# 02-POWER_SUPPLY.net
KiCad netlist of a schematic drawn in Altium Designer
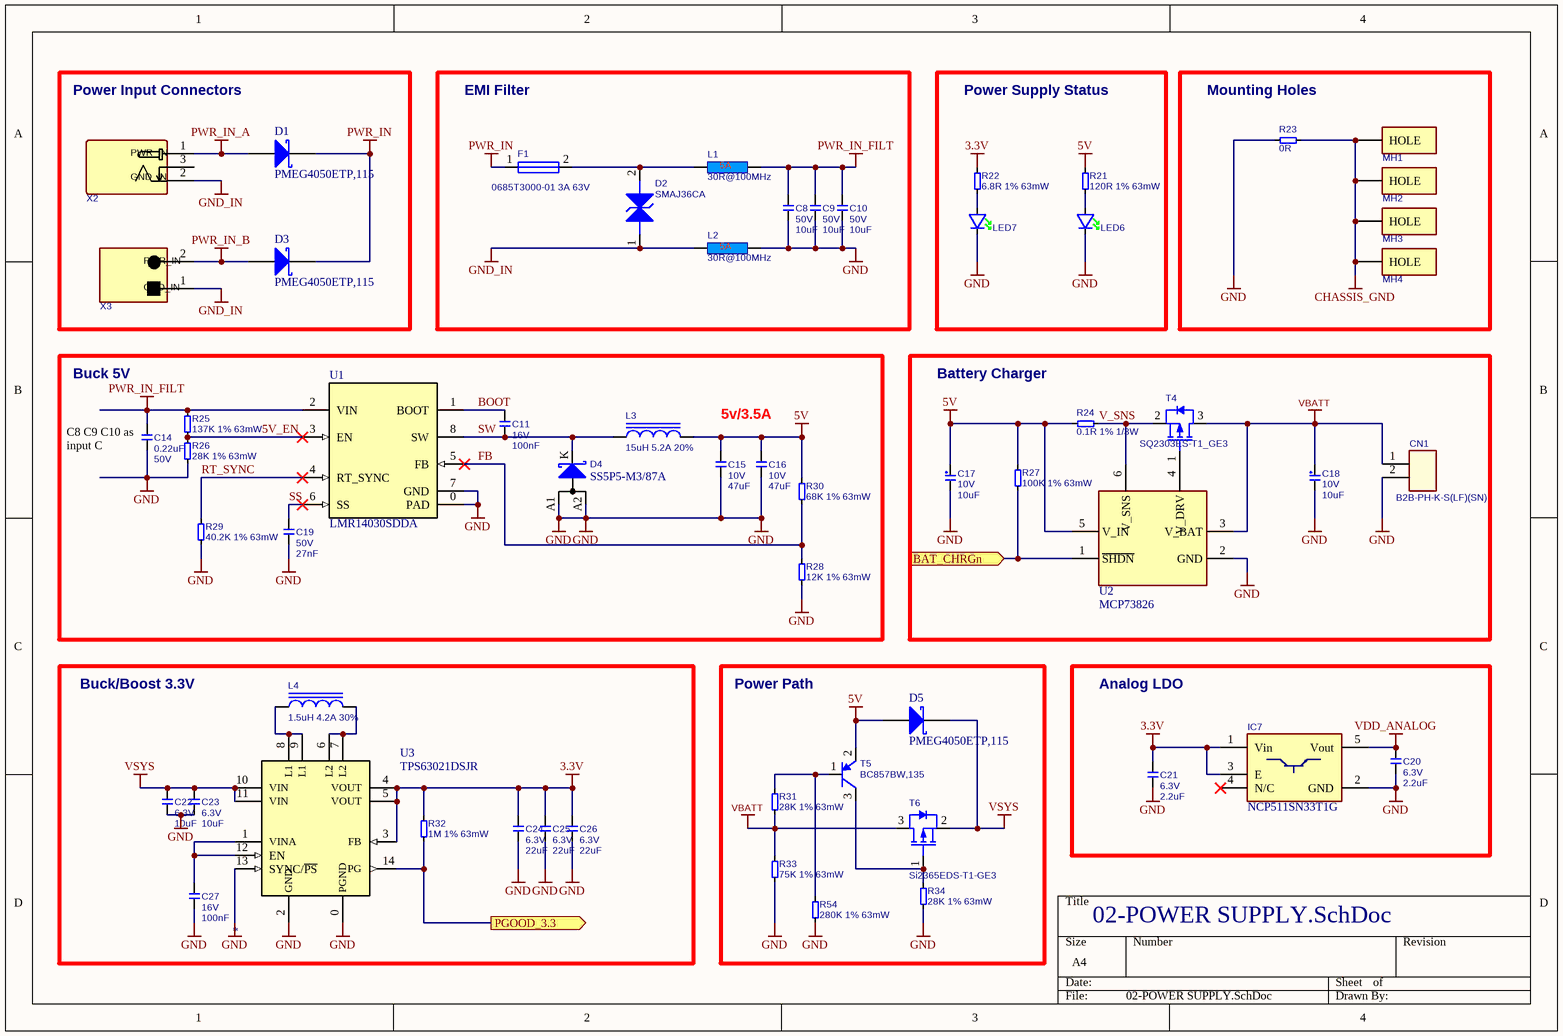
[diagram p0: 02-POWER SUPPLY.SchDoc]

(export (version "E")
  (design (tool "Eeschema 10.0.6"))
  (components
    (comp (ref "C8")
      (value "10uF")
      (footprint "CAPC3225X160N")
      (description "Capacitor Ceramic X5R 10uF 50V 20% 1210")
      (fields
        (field (name "TOLERANCE") "20%")
        (field (name "RATING") "50V")
        (field (name "Comment") "10uF 50V 20% X5R")
      )
      (libsource (lib "AI Gateway - Carrier") (part "C-10uF-50V-20%-1210"))
    )
    (comp (ref "C9")
      (value "10uF")
      (footprint "CAPC3225X160N")
      (description "Capacitor Ceramic X5R 10uF 50V 20% 1210")
      (fields
        (field (name "TOLERANCE") "20%")
        (field (name "RATING") "50V")
        (field (name "Comment") "10uF 50V 20% X5R")
      )
      (libsource (lib "AI Gateway - Carrier") (part "C-10uF-50V-20%-1210"))
    )
    (comp (ref "C10")
      (value "10uF")
      (footprint "CAPC3225X160N")
      (description "Capacitor Ceramic X5R 10uF 50V 20% 1210")
      (fields
        (field (name "TOLERANCE") "20%")
        (field (name "RATING") "50V")
        (field (name "Comment") "10uF 50V 20% X5R")
      )
      (libsource (lib "AI Gateway - Carrier") (part "C-10uF-50V-20%-1210"))
    )
    (comp (ref "C11")
      (value "100nF")
      (footprint "CAPC1005X60N")
      (description "Capacitor Ceramic X7R 100nF 16V 10% 0603")
      (fields
        (field (name "TOLERANCE") "10%")
        (field (name "RATING") "16V")
        (field (name "Comment") "100nF 16V 10% X7R")
      )
      (libsource (lib "AI Gateway - Carrier") (part "C-100nF-16V-10%-0603"))
    )
    (comp (ref "C14")
      (value "0.22uF")
      (footprint "T_CAPC0805X125N")
      (description "Capacitor Ceramic X7R 0.22uF 50V 10% 0805")
      (fields
        (field (name "TOLERANCE") "10%")
        (field (name "RATING") "50V")
        (field (name "Comment") "0.22uF 50V 10% X7R")
      )
      (libsource (lib "AI Gateway - Carrier") (part "C-0.22uF-50V-10%-0805"))
    )
    (comp (ref "C15")
      (value "47uF")
      (footprint "CAPC3225X160N")
      (description "Capacitor Ceramic X5R 47uF 10V 20% 1210")
      (fields
        (field (name "TOLERANCE") "20%")
        (field (name "RATING") "10V")
        (field (name "Comment") "47uF 10V 20% X5R")
      )
      (libsource (lib "AI Gateway - Carrier") (part "C-47uF-10V-20%-1210"))
    )
    (comp (ref "C16")
      (value "47uF")
      (footprint "CAPC3225X160N")
      (description "Capacitor Ceramic X5R 47uF 10V 20% 1210")
      (fields
        (field (name "TOLERANCE") "20%")
        (field (name "RATING") "10V")
        (field (name "Comment") "47uF 10V 20% X5R")
      )
      (libsource (lib "AI Gateway - Carrier") (part "C-47uF-10V-20%-1210"))
    )
    (comp (ref "C17")
      (value "10uF")
      (footprint "T_CAPC1206X180N")
      (description "Capacitor Tantalum 10uF 10V 20% 1206")
      (fields
        (field (name "TOLERANCE") "20%")
        (field (name "RATING") "10V")
        (field (name "Comment") "10uF 10V 20% Tantalum")
      )
      (libsource (lib "AI Gateway - Carrier") (part "C-10uF-10V-20%-1206"))
    )
    (comp (ref "C18")
      (value "10uF")
      (footprint "T_CAPC1206X180N")
      (description "Capacitor Tantalum 10uF 10V 20% 1206")
      (fields
        (field (name "TOLERANCE") "20%")
        (field (name "RATING") "10V")
        (field (name "Comment") "10uF 10V 20% Tantalum")
      )
      (libsource (lib "AI Gateway - Carrier") (part "C-10uF-10V-20%-1206"))
    )
    (comp (ref "C19")
      (value "27nF")
      (footprint "T_CAPC0603X33N")
      (description "Capacitor Ceramic X7R 27nF 50V 10% 0603")
      (fields
        (field (name "TOLERANCE") "10%")
        (field (name "RATING") "50V")
        (field (name "Comment") "27nF 50V 20% X7R")
      )
      (libsource (lib "AI Gateway - Carrier") (part "C-27nF-50V-10%-0603"))
    )
    (comp (ref "C20")
      (value "2.2uF")
      (footprint "T_CAPC0603X33N")
      (description "Capacitor Ceramic X5R 2.2uF 6.3V 20% 0603")
      (fields
        (field (name "TOLERANCE") "20%")
        (field (name "RATING") "6.3V")
        (field (name "Comment") "2.2uF 6.3V 20% X5R")
      )
      (libsource (lib "AI Gateway - Carrier") (part "C-2.2uF-6.3V-20%-0603"))
    )
    (comp (ref "C21")
      (value "2.2uF")
      (footprint "T_CAPC0603X33N")
      (description "Capacitor Ceramic X5R 2.2uF 6.3V 20% 0603")
      (fields
        (field (name "TOLERANCE") "20%")
        (field (name "RATING") "6.3V")
        (field (name "Comment") "2.2uF 6.3V 20% X5R")
      )
      (libsource (lib "AI Gateway - Carrier") (part "C-2.2uF-6.3V-20%-0603"))
    )
    (comp (ref "C22")
      (value "10uF")
      (footprint "T_CAPC0603X33N")
      (description "Capacitor Ceramic X5R 10uF 6.3V 20% 0603")
      (fields
        (field (name "TOLERANCE") "20%")
        (field (name "RATING") "6.3V")
        (field (name "Comment") "10uF 6.3V 20% X5R")
      )
      (libsource (lib "AI Gateway - Carrier") (part "C-10uF-6.3V-20%-0603"))
    )
    (comp (ref "C23")
      (value "10uF")
      (footprint "T_CAPC0603X33N")
      (description "Capacitor Ceramic X5R 10uF 6.3V 20% 0603")
      (fields
        (field (name "TOLERANCE") "20%")
        (field (name "RATING") "6.3V")
        (field (name "Comment") "10uF 6.3V 20% X5R")
      )
      (libsource (lib "AI Gateway - Carrier") (part "C-10uF-6.3V-20%-0603"))
    )
    (comp (ref "C24")
      (value "22uF")
      (footprint "T_CAPC0603X33N")
      (description "Capacitor Ceramic X5R 22uF 6.3V 20% 0603")
      (fields
        (field (name "TOLERANCE") "20%")
        (field (name "RATING") "6.3V")
        (field (name "Comment") "22uF 6.3V 20% X5R")
      )
      (libsource (lib "AI Gateway - Carrier") (part "C-22uF-6.3V-20%-0603"))
    )
    (comp (ref "C25")
      (value "22uF")
      (footprint "T_CAPC0603X33N")
      (description "Capacitor Ceramic X5R 22uF 6.3V 20% 0603")
      (fields
        (field (name "TOLERANCE") "20%")
        (field (name "RATING") "6.3V")
        (field (name "Comment") "22uF 6.3V 20% X5R")
      )
      (libsource (lib "AI Gateway - Carrier") (part "C-22uF-6.3V-20%-0603"))
    )
    (comp (ref "C26")
      (value "22uF")
      (footprint "T_CAPC0603X33N")
      (description "Capacitor Ceramic X5R 22uF 6.3V 20% 0603")
      (fields
        (field (name "TOLERANCE") "20%")
        (field (name "RATING") "6.3V")
        (field (name "Comment") "22uF 6.3V 20% X5R")
      )
      (libsource (lib "AI Gateway - Carrier") (part "C-22uF-6.3V-20%-0603"))
    )
    (comp (ref "C27")
      (value "100nF")
      (footprint "CAPC1005X60N")
      (description "Capacitor Ceramic X7R 100nF 16V 10% 0603")
      (fields
        (field (name "TOLERANCE") "10%")
        (field (name "RATING") "16V")
        (field (name "Comment") "100nF 16V 10% X7R")
      )
      (libsource (lib "AI Gateway - Carrier") (part "C-100nF-16V-10%-0603"))
    )
    (comp (ref "CN1")
      (value "B2B-PH-K-S(LF)(SN)")
      (footprint "B2B-PH-K-S(LF)(SN) - duplicate")
      (description "Connector Header Through Hole 2 position 0.079\" (2.00mm)")
      (fields (field (name "MFG") "JST") (field (name "FOOTPRINT CHECKED") "Assign OK, Footprint OK"))
      (libsource (lib "Connectors") (part "CON-JST-B2B-PH-K-S(LF)(SN)"))
    )
    (comp (ref "D1")
      (value "PMEG4050ETP,115")
      (footprint "D_SOD128")
      (description "Diode Schottky 40V 5A Surface Mount CFP5")
      (fields (field (name "MFG") "Nexperia USA Inc."))
      (libsource (lib "AI Gateway - Carrier") (part "D-NXP- PMEG4050ETP,115"))
    )
    (comp (ref "D2")
      (value "SMAJ36CA")
      (footprint "T_LITTLEFUSE_SMAJ30CA")
      (description "58.1V Clamp 6.9A Ipp Tvs Diode Surface Mount DO-214AC (SMA)")
      (fields (field (name "MFG") "Vishay") (field (name "FOOTPRINT CHECKED") "Assign OK, Footprint OK"))
      (libsource (lib "AI Gateway - Carrier") (part "D-Vishay-SMAJ36CA"))
    )
    (comp (ref "D3")
      (value "PMEG4050ETP,115")
      (footprint "D_SOD128")
      (description "Diode Schottky 40V 5A Surface Mount CFP5")
      (fields (field (name "MFG") "Nexperia USA Inc."))
      (libsource (lib "AI Gateway - Carrier") (part "D-NXP- PMEG4050ETP,115"))
    )
    (comp (ref "D4")
      (value "SS5P5-M3/87A")
      (footprint "T_DIOM_TO277A")
      (description "Diode Schottky, SS5P5-M3/87A, 50V(Vrrm), 5A(If)")
      (fields (field (name "MFG") "Vishay"))
      (libsource (lib "Passive") (part "D-Vishay-SS5P5-M3/87A"))
    )
    (comp (ref "D5")
      (value "PMEG4050ETP,115")
      (footprint "D_SOD128")
      (description "Diode Schottky 40V 5A Surface Mount CFP5")
      (fields (field (name "MFG") "Nexperia USA Inc."))
      (libsource (lib "AI Gateway - Carrier") (part "D-NXP- PMEG4050ETP,115"))
    )
    (comp (ref "F1")
      (value "0685T3000-01 3A 63V")
      (footprint "RESC3216N")
      (description "3A 63V AC 63V DC Fuse Board Mount (Cartridge Style Excluded) Surface Mount 1206 (3216 Metric)")
      (fields (field (name "MFG") "BEL") (field (name "POWER") "250mW"))
      (libsource (lib "Passive") (part "F-BEL-3A-63V"))
    )
    (comp (ref "IC7")
      (value "NCP511SN33T1G")
      (footprint "SOT95P279X142-5N")
      (description "NCP511SN33T1G LDO Regulator")
      (fields (field (name "MFG") "ON Semiconductor"))
      (libsource (lib "AIGateway") (part "IC-ON-NCP511SN33T1G"))
    )
    (comp (ref "L1")
      (value "30R@100MHz")
      (footprint "INDC1608X95N")
      (description "30 Ohms @ 100MHz 1 Power Line Ferrite Bead 0603 (1608 Metric) 5A 10mOhm")
      (fields
        (field (name "TOLERANCE") "25%")
        (field (name "MFG") "EXC-ML20A390U")
        (field (name "FOOTPRINT CHECKED") "Ok, Assign Ok")
      )
      (libsource (lib "Passive") (part "L-Murata-30R@100MHz-5A-0603"))
    )
    (comp (ref "L2")
      (value "30R@100MHz")
      (footprint "INDC1608X95N")
      (description "30 Ohms @ 100MHz 1 Power Line Ferrite Bead 0603 (1608 Metric) 5A 10mOhm")
      (fields
        (field (name "TOLERANCE") "25%")
        (field (name "MFG") "EXC-ML20A390U")
        (field (name "FOOTPRINT CHECKED") "Ok, Assign Ok")
      )
      (libsource (lib "Passive") (part "L-Murata-30R@100MHz-5A-0603"))
    )
    (comp (ref "L3")
      (value "15uH 5.2A 20%")
      (footprint "T_INDM125125X80N")
      (description "FIXED IND 15UH 5.2A 28.5MOHM SMD")
      (fields (field (name "MFG") "Bourns Inc."))
      (libsource (lib "AI Gateway - Carrier") (part "L-Bourns-SRR1280-150M"))
    )
    (comp (ref "L4")
      (value "1.5uH 4.2A 30%")
      (footprint "L_NR6028")
      (description "Inductor Ferrite core 1.5uH 4.2A 30%")
      (fields (field (name "MFG") "TAIYO YUDEN"))
      (libsource (lib "Passive") (part "L-1.5uH-4.2A-30%"))
    )
    (comp (ref "LED6")
      (value "150060GS75000")
      (footprint "LEDC1608X80N")
      (description "Green 520nm LED Indication - Discrete 3.2V 0603 (1608 Metric)")
      (fields (field (name "MFG") "Würth Elektronik"))
      (libsource (lib "AI Gateway - Carrier") (part "LED-GREEN-0603"))
    )
    (comp (ref "LED7")
      (value "150060GS75000")
      (footprint "LEDC1608X80N")
      (description "Green 520nm LED Indication - Discrete 3.2V 0603 (1608 Metric)")
      (fields (field (name "MFG") "Würth Elektronik"))
      (libsource (lib "AI Gateway - Carrier") (part "LED-GREEN-0603"))
    )
    (comp (ref "MH1")
      (value "MECH-MountingHoles")
      (footprint "T_MountingHoles")
      (description "PCB Mounting Holes, hole diemeter = 3.2mm, pad diameter = 6.2mm")
      (libsource (lib "Connectors") (part "MECH-MountingHoles"))
    )
    (comp (ref "MH2")
      (value "MECH-MountingHoles")
      (footprint "T_MountingHoles")
      (description "PCB Mounting Holes, hole diemeter = 3.2mm, pad diameter = 6.2mm")
      (libsource (lib "Connectors") (part "MECH-MountingHoles"))
    )
    (comp (ref "MH3")
      (value "MECH-MountingHoles")
      (footprint "T_MountingHoles")
      (description "PCB Mounting Holes, hole diemeter = 3.2mm, pad diameter = 6.2mm")
      (libsource (lib "Connectors") (part "MECH-MountingHoles"))
    )
    (comp (ref "MH4")
      (value "MECH-MountingHoles")
      (footprint "T_MountingHoles")
      (description "PCB Mounting Holes, hole diemeter = 3.2mm, pad diameter = 6.2mm")
      (libsource (lib "Connectors") (part "MECH-MountingHoles"))
    )
    (comp (ref "R21")
      (value "120R 1% 63mW")
      (footprint "RESC1005X40N")
      (description "Resistor 120ohm 63mW 1% 0402")
      (fields (field (name "POWER") "63mW") (field (name "TOLERANCE") "1%"))
      (libsource (lib "AI Gateway - Carrier") (part "R-120R-1%-0402"))
    )
    (comp (ref "R22")
      (value "6.8R 1% 63mW")
      (footprint "RESC1005X40N")
      (description "Resistor 6.8ohm 63mW 1% 0402")
      (fields (field (name "POWER") "63mW") (field (name "TOLERANCE") "1%"))
      (libsource (lib "AI Gateway - Carrier") (part "R-6.8R-1%-0402"))
    )
    (comp (ref "R23")
      (value "0R")
      (footprint "RESC1005X40N")
      (description "Resistor 0ohm 0402")
      (fields (field (name "POWER") "?") (field (name "TOLERANCE") "1%"))
      (libsource (lib "AI Gateway - Carrier") (part "R-0R-0402"))
    )
    (comp (ref "R24")
      (value "0.1R 1% 1/3W")
      (footprint "RESC1608N")
      (description "Resistor 0.1ohm 1/3W 1% 0603")
      (fields (field (name "POWER") "1/3") (field (name "TOLERANCE") "1%"))
      (libsource (lib "AI Gateway - Carrier") (part "R-0.1-1%-0603"))
    )
    (comp (ref "R25")
      (value "137K 1% 63mW")
      (footprint "RESC1005X40N")
      (description "Resistor 137Kohm 63mW 1% 0402")
      (fields
        (field (name "POWER") "63mW")
        (field (name "TOLERANCE") "1%")
        (field (name "SYMBOL CHECKED") "T")
      )
      (libsource (lib "AI Gateway - Carrier") (part "R-137K-1%-0402"))
    )
    (comp (ref "R26")
      (value "28K 1% 63mW")
      (footprint "RESC1005X40N")
      (description "Resistor 28Kohm 63mW 1% 0402")
      (fields
        (field (name "POWER") "63mW")
        (field (name "TOLERANCE") "1%")
        (field (name "SYMBOL CHECKED") "T")
      )
      (libsource (lib "AI Gateway - Carrier") (part "R-28K-1%-0402"))
    )
    (comp (ref "R27")
      (value "100K 1% 63mW")
      (footprint "RESC1005X40N")
      (description "Resistor 100Kohm 63mW 1% 0402")
      (fields (field (name "POWER") "63mW") (field (name "TOLERANCE") "1%"))
      (libsource (lib "AI Gateway - Carrier") (part "R-100K-1%-0402"))
    )
    (comp (ref "R28")
      (value "12K 1% 63mW")
      (footprint "RESC1005X40N")
      (description "Resistor 12Kohm 63mW 1% 0402")
      (fields
        (field (name "POWER") "63mW")
        (field (name "TOLERANCE") "1%")
        (field (name "SYMBOL CHECKED") "T")
      )
      (libsource (lib "AI Gateway - Carrier") (part "R-12K-1%-0402"))
    )
    (comp (ref "R29")
      (value "40.2K 1% 63mW")
      (footprint "RESC1005X40N")
      (description "Resistor 40.2Kohm 63mW 1% 0402")
      (fields
        (field (name "POWER") "63mW")
        (field (name "TOLERANCE") "1%")
        (field (name "SYMBOL CHECKED") "T")
      )
      (libsource (lib "AI Gateway - Carrier") (part "R-40.2K-1%-0402"))
    )
    (comp (ref "R30")
      (value "68K 1% 63mW")
      (footprint "RESC1005X40N")
      (description "Resistor 68Kohm 63mW 1% 0402")
      (fields
        (field (name "POWER") "63mW")
        (field (name "TOLERANCE") "1%")
        (field (name "SYMBOL CHECKED") "T")
      )
      (libsource (lib "AI Gateway - Carrier") (part "R-68K-1%-0402_1"))
    )
    (comp (ref "R31")
      (value "28K 1% 63mW")
      (footprint "RESC1005X40N")
      (description "Resistor 28Kohm 63mW 1% 0402")
      (fields
        (field (name "POWER") "63mW")
        (field (name "TOLERANCE") "1%")
        (field (name "SYMBOL CHECKED") "T")
      )
      (libsource (lib "AI Gateway - Carrier") (part "R-28K-1%-0402"))
    )
    (comp (ref "R32")
      (value "1M 1% 63mW")
      (footprint "RESC1005X40N")
      (description "Resistor 1Mohm 63mW 1% 0402")
      (fields (field (name "POWER") "63mW") (field (name "TOLERANCE") "1%"))
      (libsource (lib "AI Gateway - Carrier") (part "R-1M-1%-0402"))
    )
    (comp (ref "R33")
      (value "75K 1% 63mW")
      (footprint "RESC1005X40N")
      (description "Resistor 75Kohm 63mW 1% 0402")
      (fields (field (name "POWER") "63mW") (field (name "TOLERANCE") "1%"))
      (libsource (lib "AI Gateway - Carrier") (part "R-75K-1%-0402"))
    )
    (comp (ref "R34")
      (value "28K 1% 63mW")
      (footprint "RESC1005X40N")
      (description "Resistor 28Kohm 63mW 1% 0402")
      (fields
        (field (name "POWER") "63mW")
        (field (name "TOLERANCE") "1%")
        (field (name "SYMBOL CHECKED") "T")
      )
      (libsource (lib "AI Gateway - Carrier") (part "R-28K-1%-0402"))
    )
    (comp (ref "R54")
      (value "280K 1% 63mW")
      (footprint "RESC1005X40N")
      (description "Resistor 280Kohm 63mW 1% 0402")
      (fields (field (name "POWER") "63mW") (field (name "TOLERANCE") "1%"))
      (libsource (lib "AI Gateway - Carrier") (part "R-280K-1%-0402"))
    )
    (comp (ref "T4")
      (value "SQ2303ES-T1_GE3")
      (footprint "SOT95P230X110-3N")
      (description "P-Channel 30V 2.5A (Tc) 1.9W (Tc) Surface Mount TO-236 (SOT-23)")
      (fields (field (name "MFG") "VISHAY"))
      (libsource (lib "Passive") (part "T-Vishay-SQ2303ES"))
    )
    (comp (ref "T5")
      (value "BC857BW,135")
      (footprint "SOT65P210X110-3N")
      (description "PNP Transistor NXP BC857BW,135")
      (fields (field (name "MFG") "NXP"))
      (libsource (lib "Passive") (part "T-NXP-BC857BW"))
    )
    (comp (ref "T6")
      (value "Si2365EDS-T1-GE3")
      (footprint "SOT95P230X110-3N")
      (description "MOSFET, P channel Vishay Si2365EDS-T1-GE3")
      (fields (field (name "MFG") "VISHAY"))
      (libsource (lib "AI Gateway - Carrier") (part "T-Vishay-Si2365EDS"))
    )
    (comp (ref "U1")
      (value "LMR14030SDDA")
      (footprint "SOIC127P600X175-9AN-2")
      (fields (field (name "MFG") "Texas Instruments") (field (name "SYMBOL CHECKED") "DMT"))
      (libsource (lib "AI Gateway - Carrier") (part "IC-TI-LMR14030"))
    )
    (comp (ref "U2")
      (value "MCP73826")
      (footprint "SOT95P284X122-6N")
      (description "Charger IC Lithium Ion SOT-23-6")
      (fields (field (name "MFG") "Microchip") (field (name "SYMBOL CHECKED") "D"))
      (libsource (lib "AIGateway") (part "IC-Microchip-MCP73826"))
    )
    (comp (ref "U3")
      (value "TPS63021DSJR")
      (footprint "DSJ14_2P85X1P58")
      (description "Buck-Boost Switching Regulator IC Positive Fixed 3.3V 1 Output 3.5A (Switch) 14-VFDFN Exposed Pad")
      (fields
        (field (name "MFG") "Texas Instruments")
        (field (name "PARAMETER 1") "*")
        (field (name "FOOTPRINT CHECKED") "D")
      )
      (libsource (lib "AIGateway") (part "IC-TI-TPS63021"))
    )
    (comp (ref "X2")
      (value "54-00167")
      (footprint "PJ-002A")
      (description "Power Barrel Connector Jack 2.50mm ID (0.098\"), 5.50mm OD (0.217\") Through Hole, Right Angle")
      (fields (field (name "MFG") "Tensility International Corp"))
      (libsource (lib "Connectors") (part "CON-Tensility-54-00167"))
    )
    (comp (ref "X3")
      (value "1984617")
      (footprint "TERM-BLK-3.5MM")
      (description "2 Position Wire to Board Terminal Block Horizontal with Board 0.138\" (3.50mm) Through Hole")
      (fields (field (name "MFG") "Phoenix Contact"))
      (libsource (lib "Connectors") (part "CON-Phoenix-1984617-1x2-3.5mm"))
    )
  )
  (nets
    (net (code "1") (name "/5V_EN") (class "Default")
      (node (ref "R25") (pin "1") (pinfunction "1_1") (pintype "passive"))
      (node (ref "R26") (pin "2") (pinfunction "2_2") (pintype "passive"))
      (node (ref "U1") (pin "3") (pinfunction "EN_3") (pintype "input"))
    )
    (net (code "2") (name "/BAT_CHRGn") (class "Default")
      (node (ref "R27") (pin "1") (pinfunction "1_1") (pintype "passive"))
      (node (ref "U2") (pin "1") (pinfunction "~{SHDN}_1") (pintype "passive"))
    )
    (net (code "3") (name "/BOOT") (class "Default")
      (node (ref "C11") (pin "1") (pinfunction "1_1") (pintype "passive"))
      (node (ref "U1") (pin "1") (pinfunction "BOOT_1") (pintype "power_in"))
    )
    (net (code "4") (name "/FB") (class "Default")
      (node (ref "R28") (pin "1") (pinfunction "1_1") (pintype "passive"))
      (node (ref "R30") (pin "1") (pinfunction "1_1") (pintype "passive"))
      (node (ref "U1") (pin "5") (pinfunction "FB_5") (pintype "input"))
    )
    (net (code "5") (name "/PGOOD_3.3") (class "Default")
      (node (ref "R32") (pin "1") (pinfunction "1_1") (pintype "passive"))
      (node (ref "U3") (pin "14") (pinfunction "PG_14") (pintype "output"))
    )
    (net (code "6") (name "/RT_SYNC") (class "Default")
      (node (ref "R29") (pin "2") (pinfunction "2_2") (pintype "passive"))
      (node (ref "U1") (pin "4") (pinfunction "RT_SYNC_4") (pintype "input"))
    )
    (net (code "7") (name "/SS") (class "Default")
      (node (ref "C19") (pin "2") (pinfunction "2_2") (pintype "passive"))
      (node (ref "U1") (pin "6") (pinfunction "SS_6") (pintype "input"))
    )
    (net (code "8") (name "/SW") (class "Default")
      (node (ref "C11") (pin "2") (pinfunction "2_2") (pintype "passive"))
      (node (ref "D4") (pin "K") (pinfunction "K_K") (pintype "passive"))
      (node (ref "L3") (pin "1") (pinfunction "1_1") (pintype "passive"))
      (node (ref "U1") (pin "8") (pinfunction "SW_8") (pintype "power_in"))
    )
    (net (code "9") (name "/V_SNS") (class "Default")
      (node (ref "R24") (pin "1") (pinfunction "1_1") (pintype "passive"))
      (node (ref "T4") (pin "2") (pinfunction "D_2") (pintype "passive"))
      (node (ref "U2") (pin "6") (pinfunction "V_SNS_6") (pintype "passive"))
    )
    (net (code "10") (name "3.3V") (class "Default")
      (node (ref "C21") (pin "2") (pinfunction "2_2") (pintype "passive"))
      (node (ref "C24") (pin "2") (pinfunction "2_2") (pintype "passive"))
      (node (ref "C25") (pin "2") (pinfunction "2_2") (pintype "passive"))
      (node (ref "C26") (pin "2") (pinfunction "2_2") (pintype "passive"))
      (node (ref "IC7") (pin "1") (pinfunction "Vin_1") (pintype "passive"))
      (node (ref "IC7") (pin "3") (pinfunction "E_3") (pintype "passive"))
      (node (ref "R22") (pin "2") (pinfunction "2_2") (pintype "passive"))
      (node (ref "R32") (pin "2") (pinfunction "2_2") (pintype "passive"))
      (node (ref "U3") (pin "3") (pinfunction "FB_3") (pintype "input"))
      (node (ref "U3") (pin "4") (pinfunction "VOUT_4") (pintype "power_in"))
      (node (ref "U3") (pin "5") (pinfunction "VOUT_5") (pintype "power_in"))
    )
    (net (code "11") (name "5V") (class "Default")
      (node (ref "C15") (pin "2") (pinfunction "2_2") (pintype "passive"))
      (node (ref "C16") (pin "2") (pinfunction "2_2") (pintype "passive"))
      (node (ref "C17") (pin "2") (pinfunction "2_2") (pintype "passive"))
      (node (ref "D5") (pin "2") (pinfunction "A_2") (pintype "passive"))
      (node (ref "L3") (pin "2") (pinfunction "2_2") (pintype "passive"))
      (node (ref "R21") (pin "2") (pinfunction "2_2") (pintype "passive"))
      (node (ref "R24") (pin "2") (pinfunction "2_2") (pintype "passive"))
      (node (ref "R27") (pin "2") (pinfunction "2_2") (pintype "passive"))
      (node (ref "R30") (pin "2") (pinfunction "2_2") (pintype "passive"))
      (node (ref "T5") (pin "2") (pinfunction "E_2") (pintype "passive"))
      (node (ref "U2") (pin "5") (pinfunction "V_IN_5") (pintype "passive"))
    )
    (net (code "12") (name "CHASSIS_GND") (class "Default")
      (node (ref "MH1") (pin "1") (pinfunction "HOLE_1") (pintype "passive"))
      (node (ref "MH2") (pin "1") (pinfunction "HOLE_1") (pintype "passive"))
      (node (ref "MH3") (pin "1") (pinfunction "HOLE_1") (pintype "passive"))
      (node (ref "MH4") (pin "1") (pinfunction "HOLE_1") (pintype "passive"))
      (node (ref "R23") (pin "1") (pinfunction "1_1") (pintype "passive"))
    )
    (net (code "13") (name "GND") (class "Default")
      (node (ref "C10") (pin "1") (pinfunction "1_1") (pintype "passive"))
      (node (ref "C14") (pin "1") (pinfunction "1_1") (pintype "passive"))
      (node (ref "C15") (pin "1") (pinfunction "1_1") (pintype "passive"))
      (node (ref "C16") (pin "1") (pinfunction "1_1") (pintype "passive"))
      (node (ref "C17") (pin "1") (pinfunction "1_1") (pintype "passive"))
      (node (ref "C18") (pin "1") (pinfunction "1_1") (pintype "passive"))
      (node (ref "C19") (pin "1") (pinfunction "1_1") (pintype "passive"))
      (node (ref "C20") (pin "1") (pinfunction "1_1") (pintype "passive"))
      (node (ref "C21") (pin "1") (pinfunction "1_1") (pintype "passive"))
      (node (ref "C22") (pin "1") (pinfunction "1_1") (pintype "passive"))
      (node (ref "C23") (pin "1") (pinfunction "1_1") (pintype "passive"))
      (node (ref "C24") (pin "1") (pinfunction "1_1") (pintype "passive"))
      (node (ref "C25") (pin "1") (pinfunction "1_1") (pintype "passive"))
      (node (ref "C26") (pin "1") (pinfunction "1_1") (pintype "passive"))
      (node (ref "C27") (pin "1") (pinfunction "1_1") (pintype "passive"))
      (node (ref "C8") (pin "1") (pinfunction "1_1") (pintype "passive"))
      (node (ref "C9") (pin "1") (pinfunction "1_1") (pintype "passive"))
      (node (ref "CN1") (pin "2") (pinfunction "2_2") (pintype "passive"))
      (node (ref "D4") (pin "A1") (pinfunction "A1_A1") (pintype "passive"))
      (node (ref "D4") (pin "A2") (pinfunction "A2_A2") (pintype "passive"))
      (node (ref "IC7") (pin "2") (pinfunction "GND_2") (pintype "passive"))
      (node (ref "L2") (pin "1") (pinfunction "1_1") (pintype "passive"))
      (node (ref "LED6") (pin "1") (pinfunction "1_1") (pintype "passive"))
      (node (ref "LED7") (pin "1") (pinfunction "1_1") (pintype "passive"))
      (node (ref "R23") (pin "2") (pinfunction "2_2") (pintype "passive"))
      (node (ref "R26") (pin "1") (pinfunction "1_1") (pintype "passive"))
      (node (ref "R28") (pin "2") (pinfunction "2_2") (pintype "passive"))
      (node (ref "R29") (pin "1") (pinfunction "1_1") (pintype "passive"))
      (node (ref "R33") (pin "1") (pinfunction "1_1") (pintype "passive"))
      (node (ref "R34") (pin "1") (pinfunction "1_1") (pintype "passive"))
      (node (ref "R54") (pin "1") (pinfunction "1_1") (pintype "passive"))
      (node (ref "U1") (pin "0") (pinfunction "PAD_0") (pintype "power_in"))
      (node (ref "U1") (pin "7") (pinfunction "GND_7") (pintype "power_in"))
      (node (ref "U2") (pin "2") (pinfunction "GND_2") (pintype "passive"))
      (node (ref "U3") (pin "0") (pinfunction "PGND_0") (pintype "passive"))
      (node (ref "U3") (pin "13") (pinfunction "SYNC/~{PS}_13") (pintype "input"))
      (node (ref "U3") (pin "2") (pinfunction "GND_2") (pintype "power_in"))
    )
    (net (code "14") (name "GND_IN") (class "Default")
      (node (ref "D2") (pin "1") (pinfunction "ANODE_1") (pintype "passive"))
      (node (ref "L2") (pin "2") (pinfunction "2_2") (pintype "passive"))
      (node (ref "X2") (pin "2") (pinfunction "PWR_IN_2") (pintype "passive"))
      (node (ref "X3") (pin "1") (pinfunction "GND_IN_1") (pintype "passive"))
    )
    (net (code "15") (name "Net-(D2-CATHODE)") (class "Default")
      (node (ref "D2") (pin "2") (pinfunction "CATHODE_2") (pintype "passive"))
      (node (ref "F1") (pin "2") (pinfunction "2_2") (pintype "passive"))
      (node (ref "L1") (pin "2") (pinfunction "2_2") (pintype "passive"))
    )
    (net (code "16") (name "Net-(L4-Pad1)") (class "Default")
      (node (ref "L4") (pin "1") (pinfunction "1_1") (pintype "passive"))
      (node (ref "U3") (pin "8") (pinfunction "L1_8") (pintype "power_in"))
      (node (ref "U3") (pin "9") (pinfunction "L1_9") (pintype "power_in"))
    )
    (net (code "17") (name "Net-(L4-Pad2)") (class "Default")
      (node (ref "L4") (pin "2") (pinfunction "2_2") (pintype "passive"))
      (node (ref "U3") (pin "6") (pinfunction "L2_6") (pintype "power_in"))
      (node (ref "U3") (pin "7") (pinfunction "L2_7") (pintype "power_in"))
    )
    (net (code "18") (name "Net-(LED6-Pad2)") (class "Default")
      (node (ref "LED6") (pin "2") (pinfunction "2_2") (pintype "passive"))
      (node (ref "R21") (pin "1") (pinfunction "1_1") (pintype "passive"))
    )
    (net (code "19") (name "Net-(LED7-Pad2)") (class "Default")
      (node (ref "LED7") (pin "2") (pinfunction "2_2") (pintype "passive"))
      (node (ref "R22") (pin "1") (pinfunction "1_1") (pintype "passive"))
    )
    (net (code "20") (name "Net-(T4-G)") (class "Default")
      (node (ref "T4") (pin "1") (pinfunction "G_1") (pintype "passive"))
      (node (ref "U2") (pin "4") (pinfunction "V_DRV_4") (pintype "passive"))
    )
    (net (code "21") (name "Net-(T5-B)") (class "Default")
      (node (ref "R31") (pin "2") (pinfunction "2_2") (pintype "passive"))
      (node (ref "R54") (pin "2") (pinfunction "2_2") (pintype "passive"))
      (node (ref "T5") (pin "1") (pinfunction "B_1") (pintype "passive"))
    )
    (net (code "22") (name "Net-(T5-C)") (class "Default")
      (node (ref "R34") (pin "2") (pinfunction "2_2") (pintype "passive"))
      (node (ref "T5") (pin "3") (pinfunction "C_3") (pintype "passive"))
      (node (ref "T6") (pin "1") (pinfunction "G_1") (pintype "passive"))
    )
    (net (code "23") (name "Net-(U3-EN)") (class "Default")
      (node (ref "C27") (pin "2") (pinfunction "2_2") (pintype "passive"))
      (node (ref "U3") (pin "1") (pinfunction "VINA_1") (pintype "power_in"))
      (node (ref "U3") (pin "12") (pinfunction "EN_12") (pintype "input"))
    )
    (net (code "24") (name "PWR_IN") (class "Default")
      (node (ref "D1") (pin "1") (pinfunction "K_1") (pintype "passive"))
      (node (ref "D3") (pin "1") (pinfunction "K_1") (pintype "passive"))
      (node (ref "F1") (pin "1") (pinfunction "1_1") (pintype "passive"))
    )
    (net (code "25") (name "PWR_IN_A") (class "Default")
      (node (ref "D1") (pin "2") (pinfunction "A_2") (pintype "passive"))
      (node (ref "X2") (pin "1") (pinfunction "GND_IN_1") (pintype "passive"))
    )
    (net (code "26") (name "PWR_IN_B") (class "Default")
      (node (ref "D3") (pin "2") (pinfunction "A_2") (pintype "passive"))
      (node (ref "X3") (pin "2") (pinfunction "PWR_IN_2") (pintype "passive"))
    )
    (net (code "27") (name "PWR_IN_FILT") (class "Default")
      (node (ref "C10") (pin "2") (pinfunction "2_2") (pintype "passive"))
      (node (ref "C14") (pin "2") (pinfunction "2_2") (pintype "passive"))
      (node (ref "C8") (pin "2") (pinfunction "2_2") (pintype "passive"))
      (node (ref "C9") (pin "2") (pinfunction "2_2") (pintype "passive"))
      (node (ref "L1") (pin "1") (pinfunction "1_1") (pintype "passive"))
      (node (ref "R25") (pin "2") (pinfunction "2_2") (pintype "passive"))
      (node (ref "U1") (pin "2") (pinfunction "VIN_2") (pintype "power_in"))
    )
    (net (code "28") (name "VBATT") (class "Default")
      (node (ref "C18") (pin "2") (pinfunction "2_2") (pintype "passive"))
      (node (ref "CN1") (pin "1") (pinfunction "1_1") (pintype "passive"))
      (node (ref "R31") (pin "1") (pinfunction "1_1") (pintype "passive"))
      (node (ref "R33") (pin "2") (pinfunction "2_2") (pintype "passive"))
      (node (ref "T4") (pin "3") (pinfunction "S_3") (pintype "passive"))
      (node (ref "T6") (pin "3") (pinfunction "S_3") (pintype "passive"))
      (node (ref "U2") (pin "3") (pinfunction "V_BAT_3") (pintype "passive"))
    )
    (net (code "29") (name "VDD_ANALOG") (class "Default")
      (node (ref "C20") (pin "2") (pinfunction "2_2") (pintype "passive"))
      (node (ref "IC7") (pin "5") (pinfunction "Vout_5") (pintype "passive"))
    )
    (net (code "30") (name "VSYS") (class "Default")
      (node (ref "C22") (pin "2") (pinfunction "2_2") (pintype "passive"))
      (node (ref "C23") (pin "2") (pinfunction "2_2") (pintype "passive"))
      (node (ref "D5") (pin "1") (pinfunction "K_1") (pintype "passive"))
      (node (ref "T6") (pin "2") (pinfunction "D_2") (pintype "passive"))
      (node (ref "U3") (pin "10") (pinfunction "VIN_10") (pintype "power_in"))
      (node (ref "U3") (pin "11") (pinfunction "VIN_11") (pintype "power_in"))
    )
    (net (code "31") (name "unconnected-(IC7-N{slash}C-Pad4)") (class "Default")
      (node (ref "IC7") (pin "4") (pinfunction "N/C_4") (pintype "passive+no_connect"))
    )
    (net (code "32") (name "unconnected-(X2-PWR_IN-Pad3)") (class "Default")
      (node (ref "X2") (pin "3") (pinfunction "PWR_IN_3") (pintype "passive"))
    )
  )
)
